# T245-Atmega.net
KiCad netlist of a schematic drawn in EAGLE
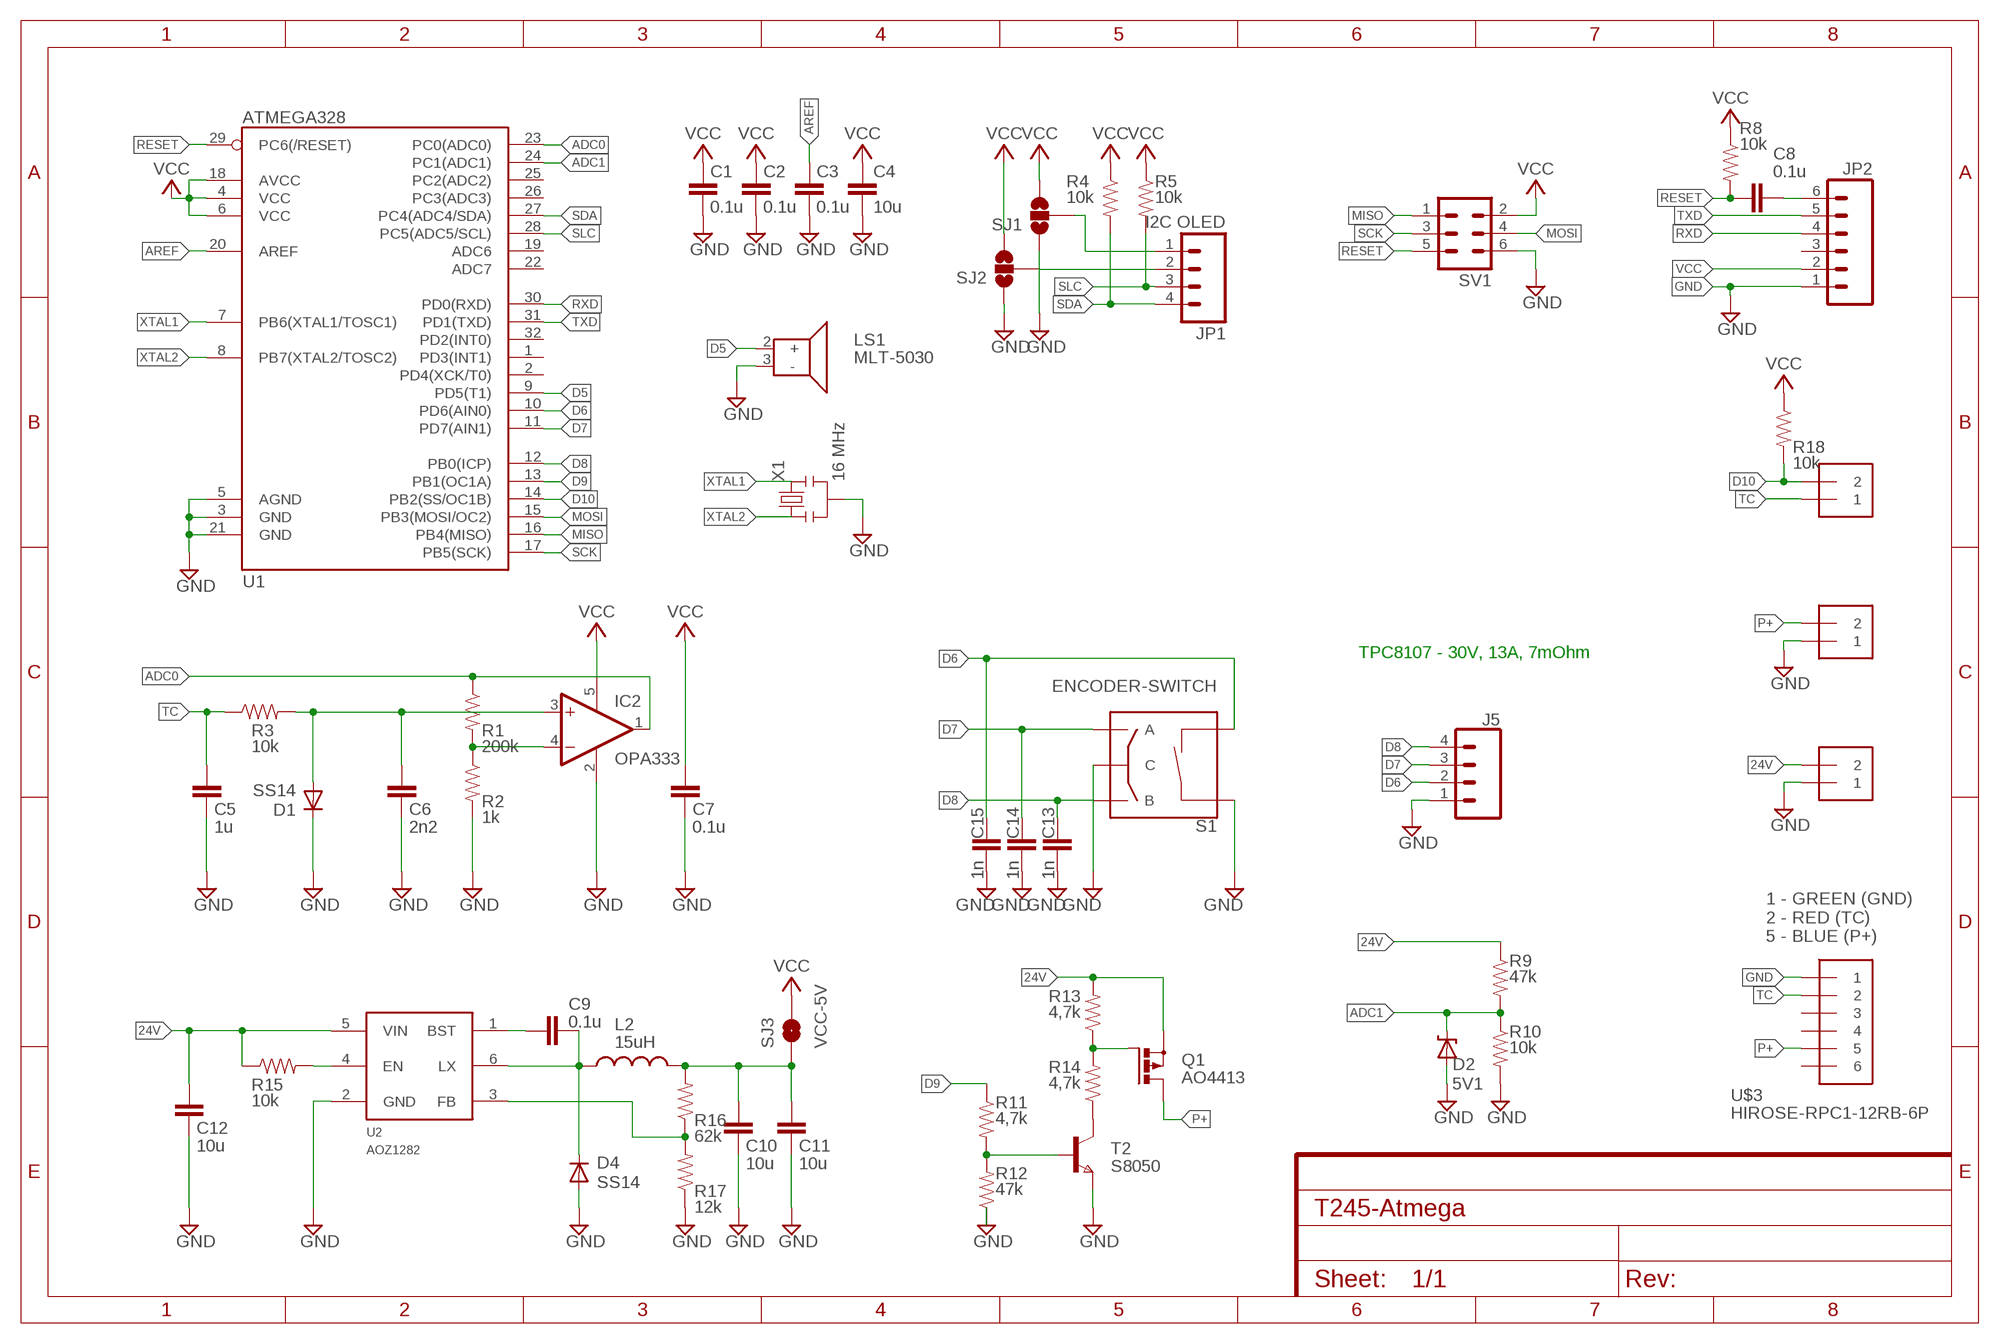
[diagram p0: schematic, sheet 1]

(export (version "E")
  (design (tool "Eeschema 10.0.6"))
  (components
    (comp (ref "C1")
      (value "0.1u")
      (footprint "eagle-import:0805")
      (libsource (lib "eagle-import") (part "CAP0805"))
    )
    (comp (ref "C2")
      (value "0.1u")
      (footprint "eagle-import:0805")
      (libsource (lib "eagle-import") (part "CAP0805"))
    )
    (comp (ref "C3")
      (value "0.1u")
      (footprint "eagle-import:0805")
      (libsource (lib "eagle-import") (part "CAP0805"))
    )
    (comp (ref "C4")
      (value "10u")
      (footprint "eagle-import:0805")
      (libsource (lib "eagle-import") (part "CAP0805"))
    )
    (comp (ref "C5")
      (value "1u")
      (footprint "eagle-import:0805")
      (libsource (lib "eagle-import") (part "CAP0805"))
    )
    (comp (ref "C6")
      (value "2n2")
      (footprint "eagle-import:0805")
      (libsource (lib "eagle-import") (part "CAP0805"))
    )
    (comp (ref "C7")
      (value "0.1u")
      (footprint "eagle-import:0805")
      (libsource (lib "eagle-import") (part "CAP0805"))
    )
    (comp (ref "C8")
      (value "0.1u")
      (footprint "eagle-import:0805")
      (libsource (lib "eagle-import") (part "CAP0805"))
    )
    (comp (ref "C9")
      (value "0.1u")
      (footprint "eagle-import:0805")
      (libsource (lib "eagle-import") (part "CAP0805"))
    )
    (comp (ref "C10")
      (value "10u")
      (footprint "eagle-import:0805")
      (libsource (lib "eagle-import") (part "CAP0805"))
    )
    (comp (ref "C11")
      (value "10u")
      (footprint "eagle-import:0805")
      (libsource (lib "eagle-import") (part "CAP0805"))
    )
    (comp (ref "C12")
      (value "10u")
      (footprint "eagle-import:1210")
      (libsource (lib "eagle-import") (part "TaaraLabs_CAP1210"))
    )
    (comp (ref "C13")
      (value "1n")
      (footprint "eagle-import:0805")
      (libsource (lib "eagle-import") (part "CAP0805"))
    )
    (comp (ref "C14")
      (value "1n")
      (footprint "eagle-import:0805")
      (libsource (lib "eagle-import") (part "CAP0805"))
    )
    (comp (ref "C15")
      (value "1n")
      (footprint "eagle-import:0805")
      (libsource (lib "eagle-import") (part "CAP0805"))
    )
    (comp (ref "D1")
      (value "SS14")
      (footprint "eagle-import:SOD-323F")
      (libsource (lib "eagle-import") (part "DIODESOD-323F"))
    )
    (comp (ref "D2")
      (value "5V1")
      (footprint "eagle-import:SOD-323")
      (libsource (lib "eagle-import") (part "DIODE-ZENER-BZT52"))
    )
    (comp (ref "D4")
      (value "SS14")
      (footprint "eagle-import:SOD-323F")
      (libsource (lib "eagle-import") (part "DIODESOD-323F"))
    )
    (comp (ref "IC2")
      (value "OPA333")
      (footprint "eagle-import:SOT23-5")
      (libsource (lib "eagle-import") (part "OPA333DBV"))
    )
    (comp (ref "J1")
      (value "HEATER")
      (footprint "eagle-import:1X2-3.5MM")
      (libsource (lib "eagle-import") (part "1X2-3.5MM"))
    )
    (comp (ref "J3")
      (value "Sensors")
      (footprint "eagle-import:1X2-3.5MM")
      (libsource (lib "eagle-import") (part "1X2-3.5MM"))
    )
    (comp (ref "J4")
      (value "24V")
      (footprint "eagle-import:1X2-3.5MM")
      (libsource (lib "eagle-import") (part "1X2-3.5MM"))
    )
    (comp (ref "J5")
      (value "M04SMALL_DIAMETER")
      (footprint "eagle-import:1X04_SMALL_DIAMETER")
      (libsource (lib "eagle-import") (part "M04SMALL_DIAMETER"))
    )
    (comp (ref "JP1")
      (value "I2C OLED")
      (footprint "eagle-import:1X04_SMALL_DIAMETER")
      (libsource (lib "eagle-import") (part "M04SMALL_DIAMETER"))
    )
    (comp (ref "JP2")
      (value "M06SIP")
      (footprint "eagle-import:1X06")
      (libsource (lib "eagle-import") (part "M06SIP"))
    )
    (comp (ref "L2")
      (value "15uH")
      (footprint "eagle-import:1210")
      (libsource (lib "eagle-import") (part "INDUCTOR1210"))
    )
    (comp (ref "LS1")
      (value "MLT-5030")
      (footprint "eagle-import:SMT0540T7R")
      (fields
        (field (name "MANUFACTURER_PART_NUMBER") "SMT-0540-T-7-R")
        (field (name "MOUSER_PART_NUMBER") "665-SMT0540T7R")
      )
      (libsource (lib "eagle-import") (part "BUZZER-0540-T-7-R"))
    )
    (comp (ref "Q1")
      (value "AO4413")
      (footprint "eagle-import:SO-08")
      (libsource (lib "eagle-import") (part "P-MOSFET-SO8"))
    )
    (comp (ref "R1")
      (value "200k")
      (footprint "eagle-import:0805")
      (libsource (lib "eagle-import") (part "RESISTOR0805-RES"))
    )
    (comp (ref "R2")
      (value "1k")
      (footprint "eagle-import:0805")
      (libsource (lib "eagle-import") (part "RESISTOR0805-RES"))
    )
    (comp (ref "R3")
      (value "10k")
      (footprint "eagle-import:0805")
      (libsource (lib "eagle-import") (part "RESISTOR0805-RES"))
    )
    (comp (ref "R4")
      (value "10k")
      (footprint "eagle-import:0805")
      (libsource (lib "eagle-import") (part "RESISTOR0805-RES"))
    )
    (comp (ref "R5")
      (value "10k")
      (footprint "eagle-import:0805")
      (libsource (lib "eagle-import") (part "RESISTOR0805-RES"))
    )
    (comp (ref "R8")
      (value "10k")
      (footprint "eagle-import:0805")
      (libsource (lib "eagle-import") (part "RESISTOR0805-RES"))
    )
    (comp (ref "R9")
      (value "47k")
      (footprint "eagle-import:0805")
      (libsource (lib "eagle-import") (part "RESISTOR0805-RES"))
    )
    (comp (ref "R10")
      (value "10k")
      (footprint "eagle-import:0805")
      (libsource (lib "eagle-import") (part "RESISTOR0805-RES"))
    )
    (comp (ref "R11")
      (value "4,7k")
      (footprint "eagle-import:0805")
      (libsource (lib "eagle-import") (part "RESISTOR0805-RES"))
    )
    (comp (ref "R12")
      (value "47k")
      (footprint "eagle-import:0805")
      (libsource (lib "eagle-import") (part "RESISTOR0805-RES"))
    )
    (comp (ref "R13")
      (value "4,7k")
      (footprint "eagle-import:0805")
      (libsource (lib "eagle-import") (part "RESISTOR0805-RES"))
    )
    (comp (ref "R14")
      (value "4,7k")
      (footprint "eagle-import:0805")
      (libsource (lib "eagle-import") (part "RESISTOR0805-RES"))
    )
    (comp (ref "R15")
      (value "10k")
      (footprint "eagle-import:0805")
      (libsource (lib "eagle-import") (part "RESISTOR0805-RES"))
    )
    (comp (ref "R16")
      (value "62k")
      (footprint "eagle-import:0805")
      (libsource (lib "eagle-import") (part "RESISTOR0805-RES"))
    )
    (comp (ref "R17")
      (value "12k")
      (footprint "eagle-import:0805")
      (libsource (lib "eagle-import") (part "RESISTOR0805-RES"))
    )
    (comp (ref "R18")
      (value "10k")
      (footprint "eagle-import:0805")
      (libsource (lib "eagle-import") (part "RESISTOR0805-RES"))
    )
    (comp (ref "S1")
      (value "ENCODER-SWITCH")
      (footprint "eagle-import:ROTARY_ENC_PLAIN")
      (libsource (lib "eagle-import") (part "ENCODER-SWITCH"))
    )
    (comp (ref "SJ1")
      (value "SOLDERJUMPER_2WAYPASTE1&2")
      (footprint "eagle-import:SJ_3_PASTE1&2")
      (libsource (lib "eagle-import") (part "SOLDERJUMPER_2WAYPASTE1&2"))
    )
    (comp (ref "SJ2")
      (value "SOLDERJUMPER_2WAYPASTE2&3")
      (footprint "eagle-import:SJ_3_PASTE2&3")
      (libsource (lib "eagle-import") (part "SOLDERJUMPER_2WAYPASTE2&3"))
    )
    (comp (ref "SJ3")
      (value "VCC-5V")
      (footprint "eagle-import:SJ_2S-NOTRACE")
      (libsource (lib "eagle-import") (part "SOLDERJUMPERNC2"))
    )
    (comp (ref "SV1")
      (value "MA03-2")
      (footprint "eagle-import:MA03-2")
      (libsource (lib "eagle-import") (part "MA03-2"))
    )
    (comp (ref "T2")
      (value "S8050")
      (footprint "eagle-import:SOT-23-DOCU")
      (libsource (lib "eagle-import") (part "NPNSOT23SOT-23-DOCU"))
    )
    (comp (ref "U$3")
      (value "HIROSE-RPC1-12RB-6P")
      (footprint "eagle-import:HIROSER-PC1-12RB-6P")
      (libsource (lib "eagle-import") (part "HIROSE-RPC1-12RB-6P"))
    )
    (comp (ref "U1")
      (value "ATMEGA328")
      (footprint "eagle-import:TQFP32-08")
      (libsource (lib "eagle-import") (part "ATMEGA168"))
    )
    (comp (ref "U2")
      (value "AOZ1282")
      (footprint "eagle-import:SOT23-6")
      (libsource (lib "eagle-import") (part "AOZ1282CI"))
    )
    (comp (ref "X1")
      (value "16 MHz")
      (footprint "eagle-import:RESONATOR-SMD")
      (libsource (lib "eagle-import") (part "RESONATORSMD"))
    )
  )
  (nets
    (net (code "1") (name "24V") (class "Default")
      (node (ref "C12") (pin "1") (pinfunction "1_1") (pintype "passive"))
      (node (ref "J4") (pin "2") (pinfunction "2_2") (pintype "passive"))
      (node (ref "Q1") (pin "1") (pinfunction "S_1") (pintype "passive"))
      (node (ref "Q1") (pin "2") (pinfunction "S_2") (pintype "passive"))
      (node (ref "Q1") (pin "3") (pinfunction "S_3") (pintype "passive"))
      (node (ref "R13") (pin "2") (pinfunction "2_2") (pintype "passive"))
      (node (ref "R15") (pin "1") (pinfunction "1_1") (pintype "passive"))
      (node (ref "R9") (pin "1") (pinfunction "1_1") (pintype "passive"))
      (node (ref "U2") (pin "5") (pinfunction "VIN_5") (pintype "bidirectional"))
    )
    (net (code "2") (name "ADC0") (class "Default")
      (node (ref "IC2") (pin "1") (pinfunction "OUT_1") (pintype "output"))
      (node (ref "R1") (pin "1") (pinfunction "1_1") (pintype "passive"))
      (node (ref "U1") (pin "23") (pinfunction "PC0(ADC0)_23") (pintype "bidirectional"))
    )
    (net (code "3") (name "ADC1") (class "Default")
      (node (ref "D2") (pin "1") (pinfunction "C_1") (pintype "passive"))
      (node (ref "R10") (pin "1") (pinfunction "1_1") (pintype "passive"))
      (node (ref "R9") (pin "2") (pinfunction "2_2") (pintype "passive"))
      (node (ref "U1") (pin "24") (pinfunction "PC1(ADC1)_24") (pintype "bidirectional"))
    )
    (net (code "4") (name "AREF") (class "Default")
      (node (ref "C3") (pin "1") (pinfunction "1_1") (pintype "passive"))
      (node (ref "U1") (pin "20") (pinfunction "AREF_20") (pintype "bidirectional"))
    )
    (net (code "5") (name "D5") (class "Default")
      (node (ref "LS1") (pin "2") (pinfunction "+_2") (pintype "bidirectional"))
      (node (ref "U1") (pin "9") (pinfunction "PD5(T1)_9") (pintype "bidirectional"))
    )
    (net (code "6") (name "D6") (class "Default")
      (node (ref "C15") (pin "2") (pinfunction "2_2") (pintype "passive"))
      (node (ref "J5") (pin "2") (pinfunction "2_2") (pintype "passive"))
      (node (ref "S1") (pin "SW-") (pinfunction "SW-_SW-") (pintype "bidirectional"))
      (node (ref "U1") (pin "10") (pinfunction "PD6(AIN0)_10") (pintype "bidirectional"))
    )
    (net (code "7") (name "D7") (class "Default")
      (node (ref "C14") (pin "2") (pinfunction "2_2") (pintype "passive"))
      (node (ref "J5") (pin "3") (pinfunction "3_3") (pintype "passive"))
      (node (ref "S1") (pin "A") (pinfunction "A_A") (pintype "bidirectional"))
      (node (ref "U1") (pin "11") (pinfunction "PD7(AIN1)_11") (pintype "bidirectional"))
    )
    (net (code "8") (name "D8") (class "Default")
      (node (ref "C13") (pin "2") (pinfunction "2_2") (pintype "passive"))
      (node (ref "J5") (pin "4") (pinfunction "4_4") (pintype "passive"))
      (node (ref "S1") (pin "B") (pinfunction "B_B") (pintype "bidirectional"))
      (node (ref "U1") (pin "12") (pinfunction "PB0(ICP)_12") (pintype "bidirectional"))
    )
    (net (code "9") (name "D9") (class "Default")
      (node (ref "R11") (pin "1") (pinfunction "1_1") (pintype "passive"))
      (node (ref "U1") (pin "13") (pinfunction "PB1(OC1A)_13") (pintype "bidirectional"))
    )
    (net (code "10") (name "D10") (class "Default")
      (node (ref "J3") (pin "2") (pinfunction "2_2") (pintype "passive"))
      (node (ref "R18") (pin "2") (pinfunction "2_2") (pintype "passive"))
      (node (ref "U1") (pin "14") (pinfunction "PB2(SS/OC1B)_14") (pintype "bidirectional"))
    )
    (net (code "11") (name "GND") (class "Default")
      (node (ref "C1") (pin "2") (pinfunction "2_2") (pintype "passive"))
      (node (ref "C10") (pin "2") (pinfunction "2_2") (pintype "passive"))
      (node (ref "C11") (pin "2") (pinfunction "2_2") (pintype "passive"))
      (node (ref "C12") (pin "2") (pinfunction "2_2") (pintype "passive"))
      (node (ref "C13") (pin "1") (pinfunction "1_1") (pintype "passive"))
      (node (ref "C14") (pin "1") (pinfunction "1_1") (pintype "passive"))
      (node (ref "C15") (pin "1") (pinfunction "1_1") (pintype "passive"))
      (node (ref "C2") (pin "2") (pinfunction "2_2") (pintype "passive"))
      (node (ref "C3") (pin "2") (pinfunction "2_2") (pintype "passive"))
      (node (ref "C4") (pin "2") (pinfunction "2_2") (pintype "passive"))
      (node (ref "C5") (pin "2") (pinfunction "2_2") (pintype "passive"))
      (node (ref "C6") (pin "2") (pinfunction "2_2") (pintype "passive"))
      (node (ref "C7") (pin "2") (pinfunction "2_2") (pintype "passive"))
      (node (ref "D1") (pin "C") (pinfunction "C_C") (pintype "passive"))
      (node (ref "D2") (pin "2") (pinfunction "A_2") (pintype "passive"))
      (node (ref "D4") (pin "A") (pinfunction "A_A") (pintype "passive"))
      (node (ref "IC2") (pin "2") (pinfunction "V-_2") (pintype "power_in"))
      (node (ref "J1") (pin "1") (pinfunction "1_1") (pintype "passive"))
      (node (ref "J4") (pin "1") (pinfunction "1_1") (pintype "passive"))
      (node (ref "J5") (pin "1") (pinfunction "1_1") (pintype "passive"))
      (node (ref "JP2") (pin "1") (pinfunction "1_1") (pintype "passive"))
      (node (ref "LS1") (pin "3") (pinfunction "-_3") (pintype "bidirectional"))
      (node (ref "R10") (pin "2") (pinfunction "2_2") (pintype "passive"))
      (node (ref "R12") (pin "1") (pinfunction "1_1") (pintype "passive"))
      (node (ref "R17") (pin "1") (pinfunction "1_1") (pintype "passive"))
      (node (ref "R2") (pin "2") (pinfunction "2_2") (pintype "passive"))
      (node (ref "S1") (pin "C") (pinfunction "C_C") (pintype "bidirectional"))
      (node (ref "S1") (pin "SW+") (pinfunction "SW+_SW+") (pintype "bidirectional"))
      (node (ref "SJ1") (pin "1") (pinfunction "1_1") (pintype "passive"))
      (node (ref "SJ2") (pin "1") (pinfunction "1_1") (pintype "passive"))
      (node (ref "SV1") (pin "6") (pinfunction "6_6") (pintype "passive"))
      (node (ref "T2") (pin "2") (pinfunction "E_2") (pintype "passive"))
      (node (ref "U$3") (pin "P$1") (pinfunction "1_P$1") (pintype "power_in"))
      (node (ref "U1") (pin "21") (pinfunction "GND_21") (pintype "bidirectional"))
      (node (ref "U1") (pin "3") (pinfunction "GND_3") (pintype "bidirectional"))
      (node (ref "U1") (pin "5") (pinfunction "AGND_5") (pintype "bidirectional"))
      (node (ref "U2") (pin "2") (pinfunction "GND_2") (pintype "bidirectional"))
      (node (ref "X1") (pin "2") (pinfunction "2_2") (pintype "passive"))
    )
    (net (code "12") (name "MISO") (class "Default")
      (node (ref "SV1") (pin "1") (pinfunction "1_1") (pintype "passive"))
      (node (ref "U1") (pin "16") (pinfunction "PB4(MISO)_16") (pintype "bidirectional"))
    )
    (net (code "13") (name "MOSI") (class "Default")
      (node (ref "SV1") (pin "4") (pinfunction "4_4") (pintype "passive"))
      (node (ref "U1") (pin "15") (pinfunction "PB3(MOSI/OC2)_15") (pintype "bidirectional"))
    )
    (net (code "14") (name "Net-(C8-Pad2)") (class "Default")
      (node (ref "C8") (pin "2") (pinfunction "2_2") (pintype "passive"))
      (node (ref "JP2") (pin "6") (pinfunction "6_6") (pintype "passive"))
    )
    (net (code "15") (name "Net-(C10-Pad1)") (class "Default")
      (node (ref "C10") (pin "1") (pinfunction "1_1") (pintype "passive"))
      (node (ref "C11") (pin "1") (pinfunction "1_1") (pintype "passive"))
      (node (ref "L2") (pin "2") (pinfunction "2_2") (pintype "passive"))
      (node (ref "R16") (pin "2") (pinfunction "2_2") (pintype "passive"))
      (node (ref "SJ3") (pin "1") (pinfunction "1_1") (pintype "passive"))
    )
    (net (code "16") (name "Net-(IC2-+IN)") (class "Default")
      (node (ref "C6") (pin "1") (pinfunction "1_1") (pintype "passive"))
      (node (ref "D1") (pin "A") (pinfunction "A_A") (pintype "passive"))
      (node (ref "IC2") (pin "3") (pinfunction "+IN_3") (pintype "input"))
      (node (ref "R3") (pin "2") (pinfunction "2_2") (pintype "passive"))
    )
    (net (code "17") (name "Net-(IC2--IN)") (class "Default")
      (node (ref "IC2") (pin "4") (pinfunction "-IN_4") (pintype "input"))
      (node (ref "R1") (pin "2") (pinfunction "2_2") (pintype "passive"))
      (node (ref "R2") (pin "1") (pinfunction "1_1") (pintype "passive"))
    )
    (net (code "18") (name "Net-(JP1-Pad1)") (class "Default")
      (node (ref "JP1") (pin "1") (pinfunction "1_1") (pintype "passive"))
      (node (ref "SJ1") (pin "2") (pinfunction "2_2") (pintype "passive"))
    )
    (net (code "19") (name "Net-(JP1-Pad2)") (class "Default")
      (node (ref "JP1") (pin "2") (pinfunction "2_2") (pintype "passive"))
      (node (ref "SJ2") (pin "2") (pinfunction "2_2") (pintype "passive"))
    )
    (net (code "20") (name "Net-(Q1-G)") (class "Default")
      (node (ref "Q1") (pin "4") (pinfunction "G_4") (pintype "passive"))
      (node (ref "R13") (pin "1") (pinfunction "1_1") (pintype "passive"))
      (node (ref "R14") (pin "2") (pinfunction "2_2") (pintype "passive"))
    )
    (net (code "21") (name "Net-(T2-B)") (class "Default")
      (node (ref "R11") (pin "2") (pinfunction "2_2") (pintype "passive"))
      (node (ref "R12") (pin "2") (pinfunction "2_2") (pintype "passive"))
      (node (ref "T2") (pin "3") (pinfunction "B_3") (pintype "passive"))
    )
    (net (code "22") (name "Net-(T2-C)") (class "Default")
      (node (ref "R14") (pin "1") (pinfunction "1_1") (pintype "passive"))
      (node (ref "T2") (pin "1") (pinfunction "C_1") (pintype "passive"))
    )
    (net (code "23") (name "Net-(U2-BST)") (class "Default")
      (node (ref "C9") (pin "1") (pinfunction "1_1") (pintype "passive"))
      (node (ref "U2") (pin "1") (pinfunction "BST_1") (pintype "bidirectional"))
    )
    (net (code "24") (name "Net-(U2-EN)") (class "Default")
      (node (ref "R15") (pin "2") (pinfunction "2_2") (pintype "passive"))
      (node (ref "U2") (pin "4") (pinfunction "EN_4") (pintype "bidirectional"))
    )
    (net (code "25") (name "Net-(U2-FB)") (class "Default")
      (node (ref "R16") (pin "1") (pinfunction "1_1") (pintype "passive"))
      (node (ref "R17") (pin "2") (pinfunction "2_2") (pintype "passive"))
      (node (ref "U2") (pin "3") (pinfunction "FB_3") (pintype "bidirectional"))
    )
    (net (code "26") (name "Net-(U2-LX)") (class "Default")
      (node (ref "C9") (pin "2") (pinfunction "2_2") (pintype "passive"))
      (node (ref "D4") (pin "C") (pinfunction "C_C") (pintype "passive"))
      (node (ref "L2") (pin "1") (pinfunction "1_1") (pintype "passive"))
      (node (ref "U2") (pin "6") (pinfunction "LX_6") (pintype "bidirectional"))
    )
    (net (code "27") (name "P+") (class "Default")
      (node (ref "J1") (pin "2") (pinfunction "2_2") (pintype "passive"))
      (node (ref "Q1") (pin "5") (pinfunction "D_5") (pintype "passive"))
      (node (ref "Q1") (pin "6") (pinfunction "D_6") (pintype "passive"))
      (node (ref "Q1") (pin "7") (pinfunction "D_7") (pintype "passive"))
      (node (ref "Q1") (pin "8") (pinfunction "D_8") (pintype "passive"))
      (node (ref "U$3") (pin "P$5") (pinfunction "5_P$5") (pintype "bidirectional"))
    )
    (net (code "28") (name "RESET") (class "Default")
      (node (ref "C8") (pin "1") (pinfunction "1_1") (pintype "passive"))
      (node (ref "R8") (pin "2") (pinfunction "2_2") (pintype "passive"))
      (node (ref "SV1") (pin "5") (pinfunction "5_5") (pintype "passive"))
      (node (ref "U1") (pin "29") (pinfunction "PC6(/RESET)_29") (pintype "bidirectional"))
    )
    (net (code "29") (name "RXD") (class "Default")
      (node (ref "JP2") (pin "4") (pinfunction "4_4") (pintype "passive"))
      (node (ref "U1") (pin "30") (pinfunction "PD0(RXD)_30") (pintype "bidirectional"))
    )
    (net (code "30") (name "SCK") (class "Default")
      (node (ref "SV1") (pin "3") (pinfunction "3_3") (pintype "passive"))
      (node (ref "U1") (pin "17") (pinfunction "PB5(SCK)_17") (pintype "bidirectional"))
    )
    (net (code "31") (name "SDA") (class "Default")
      (node (ref "JP1") (pin "4") (pinfunction "4_4") (pintype "passive"))
      (node (ref "R4") (pin "2") (pinfunction "2_2") (pintype "passive"))
      (node (ref "U1") (pin "27") (pinfunction "PC4(ADC4/SDA)_27") (pintype "bidirectional"))
    )
    (net (code "32") (name "SLC") (class "Default")
      (node (ref "JP1") (pin "3") (pinfunction "3_3") (pintype "passive"))
      (node (ref "R5") (pin "2") (pinfunction "2_2") (pintype "passive"))
      (node (ref "U1") (pin "28") (pinfunction "PC5(ADC5/SCL)_28") (pintype "bidirectional"))
    )
    (net (code "33") (name "TC") (class "Default")
      (node (ref "C5") (pin "1") (pinfunction "1_1") (pintype "passive"))
      (node (ref "J3") (pin "1") (pinfunction "1_1") (pintype "passive"))
      (node (ref "R3") (pin "1") (pinfunction "1_1") (pintype "passive"))
      (node (ref "U$3") (pin "P$2") (pinfunction "2_P$2") (pintype "power_in"))
    )
    (net (code "34") (name "TXD") (class "Default")
      (node (ref "JP2") (pin "5") (pinfunction "5_5") (pintype "passive"))
      (node (ref "U1") (pin "31") (pinfunction "PD1(TXD)_31") (pintype "bidirectional"))
    )
    (net (code "35") (name "VCC") (class "Default")
      (node (ref "C1") (pin "1") (pinfunction "1_1") (pintype "passive"))
      (node (ref "C2") (pin "1") (pinfunction "1_1") (pintype "passive"))
      (node (ref "C4") (pin "1") (pinfunction "1_1") (pintype "passive"))
      (node (ref "C7") (pin "1") (pinfunction "1_1") (pintype "passive"))
      (node (ref "IC2") (pin "5") (pinfunction "V+_5") (pintype "power_in"))
      (node (ref "JP2") (pin "2") (pinfunction "2_2") (pintype "passive"))
      (node (ref "R18") (pin "1") (pinfunction "1_1") (pintype "passive"))
      (node (ref "R4") (pin "1") (pinfunction "1_1") (pintype "passive"))
      (node (ref "R5") (pin "1") (pinfunction "1_1") (pintype "passive"))
      (node (ref "R8") (pin "1") (pinfunction "1_1") (pintype "passive"))
      (node (ref "SJ1") (pin "3") (pinfunction "3_3") (pintype "passive"))
      (node (ref "SJ2") (pin "3") (pinfunction "3_3") (pintype "passive"))
      (node (ref "SJ3") (pin "2") (pinfunction "2_2") (pintype "passive"))
      (node (ref "SV1") (pin "2") (pinfunction "2_2") (pintype "passive"))
      (node (ref "U1") (pin "18") (pinfunction "AVCC_18") (pintype "bidirectional"))
      (node (ref "U1") (pin "4") (pinfunction "VCC_4") (pintype "bidirectional"))
      (node (ref "U1") (pin "6") (pinfunction "VCC_6") (pintype "bidirectional"))
    )
    (net (code "36") (name "XTAL1") (class "Default")
      (node (ref "U1") (pin "7") (pinfunction "PB6(XTAL1/TOSC1)_7") (pintype "bidirectional"))
      (node (ref "X1") (pin "3") (pinfunction "3_3") (pintype "passive"))
    )
    (net (code "37") (name "XTAL2") (class "Default")
      (node (ref "U1") (pin "8") (pinfunction "PB7(XTAL2/TOSC2)_8") (pintype "bidirectional"))
      (node (ref "X1") (pin "1") (pinfunction "1_1") (pintype "passive"))
    )
    (net (code "38") (name "unconnected-(JP2-Pad3)") (class "Default")
      (node (ref "JP2") (pin "3") (pinfunction "3_3") (pintype "passive"))
    )
    (net (code "39") (name "unconnected-(U$3-3-PadP$3)") (class "Default")
      (node (ref "U$3") (pin "P$3") (pinfunction "3_P$3") (pintype "bidirectional"))
    )
    (net (code "40") (name "unconnected-(U$3-4-PadP$4)") (class "Default")
      (node (ref "U$3") (pin "P$4") (pinfunction "4_P$4") (pintype "bidirectional"))
    )
    (net (code "41") (name "unconnected-(U$3-6-PadP$6)") (class "Default")
      (node (ref "U$3") (pin "P$6") (pinfunction "6_P$6") (pintype "bidirectional"))
    )
    (net (code "42") (name "unconnected-(U1-ADC6-Pad19)") (class "Default")
      (node (ref "U1") (pin "19") (pinfunction "ADC6_19") (pintype "bidirectional"))
    )
    (net (code "43") (name "unconnected-(U1-ADC7-Pad22)") (class "Default")
      (node (ref "U1") (pin "22") (pinfunction "ADC7_22") (pintype "bidirectional"))
    )
    (net (code "44") (name "unconnected-(U1-PC2(ADC2)-Pad25)") (class "Default")
      (node (ref "U1") (pin "25") (pinfunction "PC2(ADC2)_25") (pintype "bidirectional"))
    )
    (net (code "45") (name "unconnected-(U1-PC3(ADC3)-Pad26)") (class "Default")
      (node (ref "U1") (pin "26") (pinfunction "PC3(ADC3)_26") (pintype "bidirectional"))
    )
    (net (code "46") (name "unconnected-(U1-PD2(INT0)-Pad32)") (class "Default")
      (node (ref "U1") (pin "32") (pinfunction "PD2(INT0)_32") (pintype "bidirectional"))
    )
    (net (code "47") (name "unconnected-(U1-PD3(INT1)-Pad1)") (class "Default")
      (node (ref "U1") (pin "1") (pinfunction "PD3(INT1)_1") (pintype "bidirectional"))
    )
    (net (code "48") (name "unconnected-(U1-PD4(XCK{slash}T0)-Pad2)") (class "Default")
      (node (ref "U1") (pin "2") (pinfunction "PD4(XCK/T0)_2") (pintype "bidirectional"))
    )
  )
)
